# RampPLLWaveyRadar.net
KiCad netlist of a schematic drawn in Altium Designer
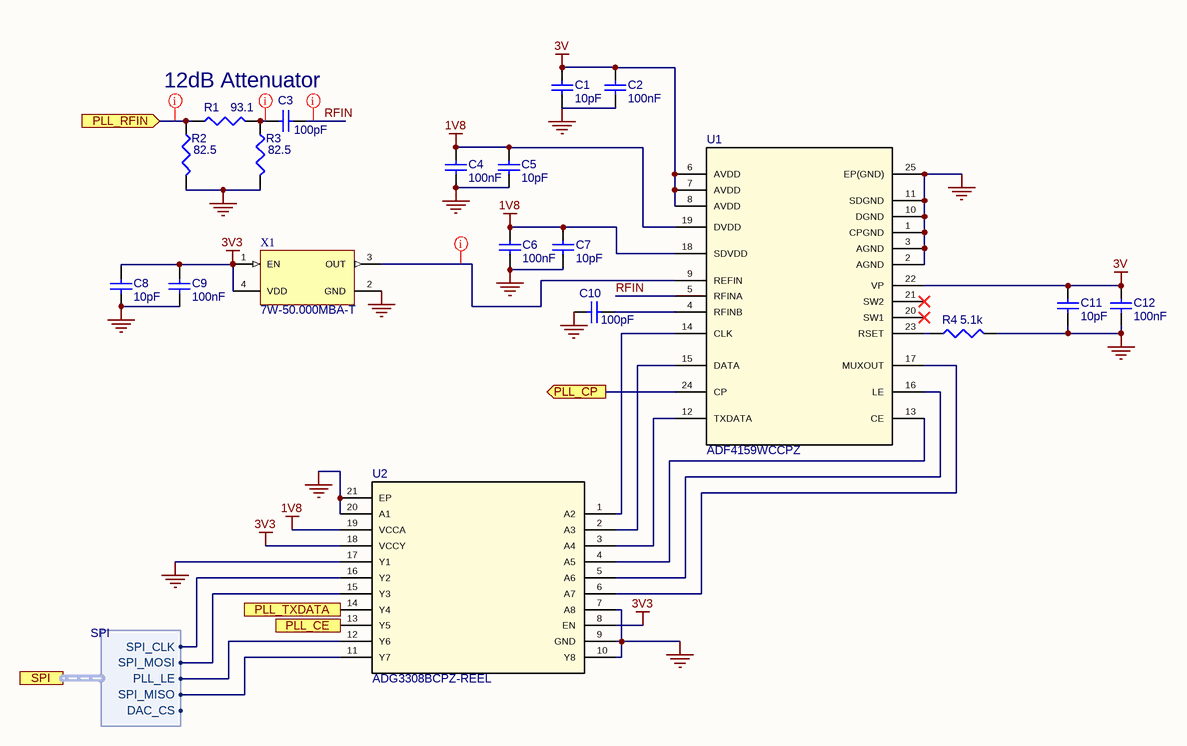
[diagram p0: RampPLLWaveyRadar.SchDoc]

(export (version "E")
  (design (tool "Eeschema 10.0.6"))
  (components
    (comp (ref "C1")
      (value "10pF")
      (footprint "CAPC1005X55X30LL05T10")
      (description "Chip Capacitor, 10 pF, +/- 0.25 pF, 50 V, 0402 (1005 Metric)")
      (fields
        (field (name "TOLERANCE") "0.25%")
        (field (name "Comment") "Capacitor 10 pF +/- 0.25 pF 50 V 0402")
      )
      (libsource (lib "University of South Florida") (part "CAP-NP-2"))
    )
    (comp (ref "C2")
      (value "100nF")
      (footprint "CAPC0402(1005)60_L")
      (description "Chip Capacitor, 100nF +/-20%, 10V, 0402, Thickness 0.6 mm")
      (fields (field (name "TOLERANCE") "20%") (field (name "Comment") "Capacitor 100nF +/-20% 10V 0402"))
      (libsource (lib "University of South Florida") (part "CAP-NP-2"))
    )
    (comp (ref "C3")
      (value "100pF")
      (footprint "CAPC1005X56X25LL10T15")
      (fields (field (name "Comment") "04023A101JAT2A"))
      (libsource (lib "University of South Florida") (part "CAP-NP-2"))
    )
    (comp (ref "C4")
      (value "100nF")
      (footprint "CAPC0402(1005)60_L")
      (description "Chip Capacitor, 100nF +/-20%, 10V, 0402, Thickness 0.6 mm")
      (fields (field (name "TOLERANCE") "20%") (field (name "Comment") "Capacitor 100nF +/-20% 10V 0402"))
      (libsource (lib "University of South Florida") (part "CAP-NP-2"))
    )
    (comp (ref "C5")
      (value "10pF")
      (footprint "CAPC1005X55X30LL05T10")
      (description "Chip Capacitor, 10 pF, +/- 0.25 pF, 50 V, 0402 (1005 Metric)")
      (fields
        (field (name "TOLERANCE") "0.25%")
        (field (name "Comment") "Capacitor 10 pF +/- 0.25 pF 50 V 0402")
      )
      (libsource (lib "University of South Florida") (part "CAP-NP-2"))
    )
    (comp (ref "C6")
      (value "100nF")
      (footprint "CAPC0402(1005)60_L")
      (description "Chip Capacitor, 100nF +/-20%, 10V, 0402, Thickness 0.6 mm")
      (fields (field (name "TOLERANCE") "20%") (field (name "Comment") "Capacitor 100nF +/-20% 10V 0402"))
      (libsource (lib "University of South Florida") (part "CAP-NP-2"))
    )
    (comp (ref "C7")
      (value "10pF")
      (footprint "CAPC1005X55X30LL05T10")
      (description "Chip Capacitor, 10 pF, +/- 0.25 pF, 50 V, 0402 (1005 Metric)")
      (fields
        (field (name "TOLERANCE") "0.25%")
        (field (name "Comment") "Capacitor 10 pF +/- 0.25 pF 50 V 0402")
      )
      (libsource (lib "University of South Florida") (part "CAP-NP-2"))
    )
    (comp (ref "C8")
      (value "10pF")
      (footprint "CAPC1005X55X30LL05T10")
      (description "Chip Capacitor, 10 pF, +/- 0.25 pF, 50 V, 0402 (1005 Metric)")
      (fields
        (field (name "TOLERANCE") "0.25%")
        (field (name "Comment") "Capacitor 10 pF +/- 0.25 pF 50 V 0402")
      )
      (libsource (lib "University of South Florida") (part "CAP-NP-2"))
    )
    (comp (ref "C9")
      (value "100nF")
      (footprint "CAPC0402(1005)60_L")
      (description "Chip Capacitor, 100nF +/-20%, 10V, 0402, Thickness 0.6 mm")
      (fields (field (name "TOLERANCE") "20%") (field (name "Comment") "Capacitor 100nF +/-20% 10V 0402"))
      (libsource (lib "University of South Florida") (part "CAP-NP-2"))
    )
    (comp (ref "C10")
      (value "100pF")
      (footprint "CAPC1005X56X25LL10T15")
      (fields (field (name "Comment") "04023A101JAT2A"))
      (libsource (lib "University of South Florida") (part "CAP-NP-2"))
    )
    (comp (ref "C11")
      (value "10pF")
      (footprint "CAPC1005X55X30LL05T10")
      (description "Chip Capacitor, 10 pF, +/- 0.25 pF, 50 V, 0402 (1005 Metric)")
      (fields
        (field (name "TOLERANCE") "0.25%")
        (field (name "Comment") "Capacitor 10 pF +/- 0.25 pF 50 V 0402")
      )
      (libsource (lib "University of South Florida") (part "CAP-NP-2"))
    )
    (comp (ref "C12")
      (value "100nF")
      (footprint "CAPC0402(1005)60_L")
      (description "Chip Capacitor, 100nF +/-20%, 10V, 0402, Thickness 0.6 mm")
      (fields (field (name "TOLERANCE") "20%") (field (name "Comment") "Capacitor 100nF +/-20% 10V 0402"))
      (libsource (lib "University of South Florida") (part "CAP-NP-2"))
    )
    (comp (ref "R1")
      (value "93.1")
      (footprint "RESC1005X40X25LL10T10")
      (description "Thick Film Resistors 93.1OHM 1/16WATT 1%")
      (fields (field (name "Comment") "CR0402-FX-93R1GLF"))
      (libsource (lib "University of South Florida") (part "ResistorSymbol"))
    )
    (comp (ref "R2")
      (value "82.5")
      (footprint "RESC1005X40X25NL05T05")
      (fields (field (name "Comment") "ERJ-2RKF82R5X"))
      (libsource (lib "University of South Florida") (part "ResistorSymbol"))
    )
    (comp (ref "R3")
      (value "82.5")
      (footprint "RESC1005X40X25NL05T05")
      (fields (field (name "Comment") "ERJ-2RKF82R5X"))
      (libsource (lib "University of South Florida") (part "ResistorSymbol"))
    )
    (comp (ref "R4")
      (value "5.1k")
      (footprint "RESC1005X40X25NL05T05")
      (fields (field (name "Comment") "ERJ-2RKF5101X"))
      (libsource (lib "University of South Florida") (part "ResistorSymbol"))
    )
    (comp (ref "U1")
      (value "ADF4159WCCPZ")
      (footprint "CP_24_10")
      (description "No Description Available")
      (libsource (lib "ADF4159WCCPZ") (part "ADF4159WCCPZ"))
    )
    (comp (ref "U2")
      (value "ADG3308BCPZ-REEL")
      (footprint "CP_20_1_ADI")
      (description "No Description Available")
      (fields (field (name "COPYRIGHT") "Copyright (C) 2021 Accelerated Designs. All rights reserved"))
      (libsource (lib "University of South Florida") (part "ADG3308BCPZ-REEL"))
    )
    (comp (ref "X1")
      (value "7W-50.000MBA-T")
      (footprint "TXC-L500W700H130-4_V")
      (libsource (lib "University of South Florida") (part "TXC-7W-50_000MBA-T-4"))
    )
  )
  (nets
    (net (code "2") (name "/PLL_CE") (class "Default")
      (node (ref "U2") (pin "13") (pinfunction "Y5_13") (pintype "passive"))
    )
    (net (code "3") (name "/PLL_CP") (class "Default")
      (node (ref "U1") (pin "24") (pinfunction "CP_24") (pintype "passive"))
    )
    (net (code "4") (name "/PLL_LE") (class "Default")
      (node (ref "U2") (pin "12") (pinfunction "Y6_12") (pintype "passive"))
    )
    (net (code "5") (name "/PLL_RFIN") (class "Default")
      (node (ref "R1") (pin "1") (pinfunction "1_1") (pintype "passive"))
      (node (ref "R2") (pin "1") (pinfunction "1_1") (pintype "passive"))
    )
    (net (code "6") (name "/PLL_TXDATA") (class "Default")
      (node (ref "U2") (pin "14") (pinfunction "Y4_14") (pintype "passive"))
    )
    (net (code "7") (name "/RFIN") (class "Default")
      (node (ref "C3") (pin "2") (pinfunction "2_2") (pintype "passive"))
      (node (ref "U1") (pin "5") (pinfunction "RFINA_5") (pintype "passive"))
    )
    (net (code "8") (name "/SPI_CLK") (class "Default")
      (node (ref "U2") (pin "16") (pinfunction "Y2_16") (pintype "passive"))
    )
    (net (code "9") (name "/SPI_MISO") (class "Default")
      (node (ref "U2") (pin "11") (pinfunction "Y7_11") (pintype "passive"))
    )
    (net (code "10") (name "/SPI_MOSI") (class "Default")
      (node (ref "U2") (pin "15") (pinfunction "Y3_15") (pintype "passive"))
    )
    (net (code "12") (name "1V8") (class "Default")
      (node (ref "C4") (pin "2") (pinfunction "2_2") (pintype "passive"))
      (node (ref "C5") (pin "2") (pinfunction "2_2") (pintype "passive"))
      (node (ref "C6") (pin "2") (pinfunction "2_2") (pintype "passive"))
      (node (ref "C7") (pin "2") (pinfunction "2_2") (pintype "passive"))
      (node (ref "U1") (pin "18") (pinfunction "SDVDD_18") (pintype "passive"))
      (node (ref "U1") (pin "19") (pinfunction "DVDD_19") (pintype "passive"))
      (node (ref "U2") (pin "19") (pinfunction "VCCA_19") (pintype "power_in"))
    )
    (net (code "13") (name "3V") (class "Default")
      (node (ref "C1") (pin "2") (pinfunction "2_2") (pintype "passive"))
      (node (ref "C11") (pin "2") (pinfunction "2_2") (pintype "passive"))
      (node (ref "C12") (pin "2") (pinfunction "2_2") (pintype "passive"))
      (node (ref "C2") (pin "2") (pinfunction "2_2") (pintype "passive"))
      (node (ref "U1") (pin "22") (pinfunction "VP_22") (pintype "passive"))
      (node (ref "U1") (pin "6") (pinfunction "AVDD_6") (pintype "passive"))
      (node (ref "U1") (pin "7") (pinfunction "AVDD_7") (pintype "passive"))
      (node (ref "U1") (pin "8") (pinfunction "AVDD_8") (pintype "passive"))
    )
    (net (code "14") (name "3V3") (class "Default")
      (node (ref "C8") (pin "2") (pinfunction "2_2") (pintype "passive"))
      (node (ref "C9") (pin "2") (pinfunction "2_2") (pintype "passive"))
      (node (ref "U2") (pin "18") (pinfunction "VCCY_18") (pintype "power_in"))
      (node (ref "U2") (pin "8") (pinfunction "EN_8") (pintype "passive"))
      (node (ref "X1") (pin "1") (pinfunction "EN_1") (pintype "input"))
      (node (ref "X1") (pin "4") (pinfunction "VDD_4") (pintype "power_in"))
    )
    (net (code "15") (name "GND") (class "Default")
      (node (ref "C1") (pin "1") (pinfunction "1_1") (pintype "passive"))
      (node (ref "C10") (pin "1") (pinfunction "1_1") (pintype "passive"))
      (node (ref "C11") (pin "1") (pinfunction "1_1") (pintype "passive"))
      (node (ref "C12") (pin "1") (pinfunction "1_1") (pintype "passive"))
      (node (ref "C2") (pin "1") (pinfunction "1_1") (pintype "passive"))
      (node (ref "C4") (pin "1") (pinfunction "1_1") (pintype "passive"))
      (node (ref "C5") (pin "1") (pinfunction "1_1") (pintype "passive"))
      (node (ref "C6") (pin "1") (pinfunction "1_1") (pintype "passive"))
      (node (ref "C7") (pin "1") (pinfunction "1_1") (pintype "passive"))
      (node (ref "C8") (pin "1") (pinfunction "1_1") (pintype "passive"))
      (node (ref "C9") (pin "1") (pinfunction "1_1") (pintype "passive"))
      (node (ref "R2") (pin "2") (pinfunction "2_2") (pintype "passive"))
      (node (ref "R3") (pin "2") (pinfunction "2_2") (pintype "passive"))
      (node (ref "R4") (pin "2") (pinfunction "2_2") (pintype "passive"))
      (node (ref "U1") (pin "1") (pinfunction "CPGND_1") (pintype "passive"))
      (node (ref "U1") (pin "10") (pinfunction "DGND_10") (pintype "passive"))
      (node (ref "U1") (pin "11") (pinfunction "SDGND_11") (pintype "passive"))
      (node (ref "U1") (pin "2") (pinfunction "AGND_2") (pintype "passive"))
      (node (ref "U1") (pin "25") (pinfunction "EP(GND)_25") (pintype "passive"))
      (node (ref "U1") (pin "3") (pinfunction "AGND_3") (pintype "passive"))
      (node (ref "U2") (pin "10") (pinfunction "Y8_10") (pintype "passive"))
      (node (ref "U2") (pin "17") (pinfunction "Y1_17") (pintype "passive"))
      (node (ref "U2") (pin "20") (pinfunction "A1_20") (pintype "passive"))
      (node (ref "U2") (pin "21") (pinfunction "EP_21") (pintype "passive"))
      (node (ref "U2") (pin "7") (pinfunction "A8_7") (pintype "passive"))
      (node (ref "U2") (pin "9") (pinfunction "GND_9") (pintype "passive"))
      (node (ref "X1") (pin "2") (pinfunction "GND_2") (pintype "power_in"))
    )
    (net (code "16") (name "Net-(C3-Pad1)") (class "Default")
      (node (ref "C3") (pin "1") (pinfunction "1_1") (pintype "passive"))
      (node (ref "R1") (pin "2") (pinfunction "2_2") (pintype "passive"))
      (node (ref "R3") (pin "1") (pinfunction "1_1") (pintype "passive"))
    )
    (net (code "17") (name "Net-(U1-CE)") (class "Default")
      (node (ref "U1") (pin "13") (pinfunction "CE_13") (pintype "passive"))
      (node (ref "U2") (pin "4") (pinfunction "A5_4") (pintype "passive"))
    )
    (net (code "18") (name "Net-(U1-CLK)") (class "Default")
      (node (ref "U1") (pin "14") (pinfunction "CLK_14") (pintype "passive"))
      (node (ref "U2") (pin "1") (pinfunction "A2_1") (pintype "passive"))
    )
    (net (code "19") (name "Net-(U1-DATA)") (class "Default")
      (node (ref "U1") (pin "15") (pinfunction "DATA_15") (pintype "passive"))
      (node (ref "U2") (pin "2") (pinfunction "A3_2") (pintype "passive"))
    )
    (net (code "20") (name "Net-(U1-LE)") (class "Default")
      (node (ref "U1") (pin "16") (pinfunction "LE_16") (pintype "passive"))
      (node (ref "U2") (pin "5") (pinfunction "A6_5") (pintype "passive"))
    )
    (net (code "21") (name "Net-(U1-MUXOUT)") (class "Default")
      (node (ref "U1") (pin "17") (pinfunction "MUXOUT_17") (pintype "passive"))
      (node (ref "U2") (pin "6") (pinfunction "A7_6") (pintype "passive"))
    )
    (net (code "22") (name "Net-(U1-REFIN)") (class "Default")
      (node (ref "U1") (pin "9") (pinfunction "REFIN_9") (pintype "passive"))
      (node (ref "X1") (pin "3") (pinfunction "OUT_3") (pintype "output"))
    )
    (net (code "23") (name "Net-(U1-RFINB)") (class "Default")
      (node (ref "C10") (pin "2") (pinfunction "2_2") (pintype "passive"))
      (node (ref "U1") (pin "4") (pinfunction "RFINB_4") (pintype "passive"))
    )
    (net (code "24") (name "Net-(U1-RSET)") (class "Default")
      (node (ref "R4") (pin "1") (pinfunction "1_1") (pintype "passive"))
      (node (ref "U1") (pin "23") (pinfunction "RSET_23") (pintype "passive"))
    )
    (net (code "25") (name "Net-(U1-TXDATA)") (class "Default")
      (node (ref "U1") (pin "12") (pinfunction "TXDATA_12") (pintype "passive"))
      (node (ref "U2") (pin "3") (pinfunction "A4_3") (pintype "passive"))
    )
    (net (code "26") (name "unconnected-(U1-SW1-Pad20)") (class "Default")
      (node (ref "U1") (pin "20") (pinfunction "SW1_20") (pintype "passive+no_connect"))
    )
    (net (code "27") (name "unconnected-(U1-SW2-Pad21)") (class "Default")
      (node (ref "U1") (pin "21") (pinfunction "SW2_21") (pintype "passive+no_connect"))
    )
  )
)
